# board.net
KiCad netlist of a schematic drawn in EAGLE
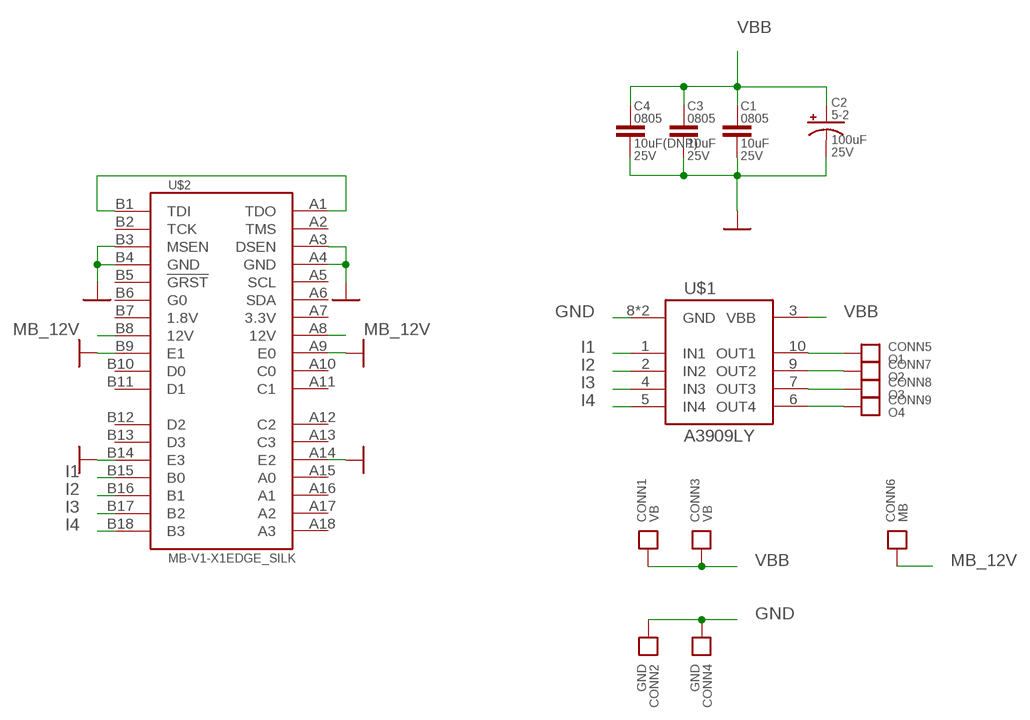
[diagram p0: schematic, sheet 1]

(export (version "E")
  (design (tool "Eeschema 10.0.6"))
  (components
    (comp (ref "C1")
      (value "10uF")
      (footprint "eagle-import:0805-CAP")
      (fields (field (name "VOLTAGE") "6.3V") (field (name "VOLTAGE_1") "25V"))
      (libsource (lib "eagle-import") (part "CAP0805"))
    )
    (comp (ref "C2")
      (value "100uF")
      (footprint "eagle-import:CAP-5-2")
      (fields (field (name "VOLTAGE") "6.3V") (field (name "VOLTAGE_1") "25V"))
      (libsource (lib "eagle-import") (part "CAP_POLPTH-5-2"))
    )
    (comp (ref "C3")
      (value "10uF")
      (footprint "eagle-import:0805-CAP")
      (fields (field (name "VOLTAGE") "6.3V") (field (name "VOLTAGE_1") "25V"))
      (libsource (lib "eagle-import") (part "CAP0805"))
    )
    (comp (ref "C4")
      (value "10uF(DNP)")
      (footprint "eagle-import:0805-CAP")
      (fields (field (name "VOLTAGE") "6.3V") (field (name "VOLTAGE_1") "25V"))
      (libsource (lib "eagle-import") (part "CAP0805"))
    )
    (comp (ref "CONN1")
      (value "VB")
      (footprint "eagle-import:SCREW_5MM")
      (libsource (lib "eagle-import") (part "CONNECTORSCREW_5MM"))
    )
    (comp (ref "CONN2")
      (value "GND")
      (footprint "eagle-import:SCREW_5MM")
      (libsource (lib "eagle-import") (part "CONNECTORSCREW_5MM"))
    )
    (comp (ref "CONN3")
      (value "VB")
      (footprint "eagle-import:SCREW_2.5MM")
      (libsource (lib "eagle-import") (part "CONNECTORSCREW_2.5MM"))
    )
    (comp (ref "CONN4")
      (value "GND")
      (footprint "eagle-import:SCREW_2.5MM")
      (libsource (lib "eagle-import") (part "CONNECTORSCREW_2.5MM"))
    )
    (comp (ref "CONN5")
      (value "O1")
      (footprint "eagle-import:SCREW_2.5MM")
      (libsource (lib "eagle-import") (part "CONNECTORSCREW_2.5MM"))
    )
    (comp (ref "CONN6")
      (value "MB")
      (footprint "eagle-import:SCREW_2.5MM")
      (libsource (lib "eagle-import") (part "CONNECTORSCREW_2.5MM"))
    )
    (comp (ref "CONN7")
      (value "O2")
      (footprint "eagle-import:SCREW_2.5MM")
      (libsource (lib "eagle-import") (part "CONNECTORSCREW_2.5MM"))
    )
    (comp (ref "CONN8")
      (value "O3")
      (footprint "eagle-import:SCREW_2.5MM")
      (libsource (lib "eagle-import") (part "CONNECTORSCREW_2.5MM"))
    )
    (comp (ref "CONN9")
      (value "O4")
      (footprint "eagle-import:SCREW_2.5MM")
      (libsource (lib "eagle-import") (part "CONNECTORSCREW_2.5MM"))
    )
    (comp (ref "U$1")
      (value "A3909LY")
      (footprint "eagle-import:MSOP10")
      (libsource (lib "eagle-import") (part "A3909LY"))
    )
    (comp (ref "U$2")
      (value "MB-V1-X1EDGE_SILK")
      (footprint "eagle-import:MB-V1-X1-EDGE")
      (libsource (lib "eagle-import") (part "MB-V1-X1EDGE_SILK"))
    )
  )
  (nets
    (net (code "1") (name "/I1") (class "Default")
      (node (ref "U$1") (pin "1") (pinfunction "IN1_1") (pintype "bidirectional"))
      (node (ref "U$2") (pin "B15") (pinfunction "B0_B15") (pintype "bidirectional"))
    )
    (net (code "2") (name "/I2") (class "Default")
      (node (ref "U$1") (pin "2") (pinfunction "IN2_2") (pintype "bidirectional"))
      (node (ref "U$2") (pin "B16") (pinfunction "B1_B16") (pintype "bidirectional"))
    )
    (net (code "3") (name "/I3") (class "Default")
      (node (ref "U$1") (pin "4") (pinfunction "IN3_4") (pintype "bidirectional"))
      (node (ref "U$2") (pin "B17") (pinfunction "B2_B17") (pintype "bidirectional"))
    )
    (net (code "4") (name "/I4") (class "Default")
      (node (ref "U$1") (pin "5") (pinfunction "IN4_5") (pintype "bidirectional"))
      (node (ref "U$2") (pin "B18") (pinfunction "B3_B18") (pintype "bidirectional"))
    )
    (net (code "5") (name "/MB_12V") (class "Default")
      (node (ref "CONN6") (pin "P") (pinfunction "P_P") (pintype "bidirectional"))
      (node (ref "U$2") (pin "A8") (pinfunction "12V_A8") (pintype "bidirectional"))
      (node (ref "U$2") (pin "B8") (pinfunction "12V_B8") (pintype "bidirectional"))
    )
    (net (code "6") (name "/VBB") (class "Default")
      (node (ref "C1") (pin "1") (pinfunction "1_1") (pintype "passive"))
      (node (ref "C2") (pin "1") (pinfunction "+_1") (pintype "passive"))
      (node (ref "C3") (pin "1") (pinfunction "1_1") (pintype "passive"))
      (node (ref "C4") (pin "1") (pinfunction "1_1") (pintype "passive"))
      (node (ref "CONN1") (pin "P$1") (pinfunction "P_P$1") (pintype "bidirectional"))
      (node (ref "CONN3") (pin "P") (pinfunction "P_P") (pintype "bidirectional"))
      (node (ref "U$1") (pin "3") (pinfunction "VBB_3") (pintype "input"))
    )
    (net (code "7") (name "GND") (class "Default")
      (node (ref "C1") (pin "2") (pinfunction "2_2") (pintype "passive"))
      (node (ref "C2") (pin "2") (pinfunction "-_2") (pintype "passive"))
      (node (ref "C3") (pin "2") (pinfunction "2_2") (pintype "passive"))
      (node (ref "C4") (pin "2") (pinfunction "2_2") (pintype "passive"))
      (node (ref "CONN2") (pin "P$1") (pinfunction "P_P$1") (pintype "bidirectional"))
      (node (ref "CONN4") (pin "P") (pinfunction "P_P") (pintype "bidirectional"))
      (node (ref "U$1") (pin "8") (pinfunction "GND_8") (pintype "input"))
      (node (ref "U$1") (pin "PAD") (pinfunction "GND_PAD") (pintype "input"))
      (node (ref "U$2") (pin "A14") (pinfunction "E2_A14") (pintype "bidirectional"))
      (node (ref "U$2") (pin "A3") (pinfunction "DSEN_A3") (pintype "bidirectional"))
      (node (ref "U$2") (pin "A4") (pinfunction "GND_A4") (pintype "input"))
      (node (ref "U$2") (pin "A9") (pinfunction "E0_A9") (pintype "bidirectional"))
      (node (ref "U$2") (pin "B14") (pinfunction "E3_B14") (pintype "bidirectional"))
      (node (ref "U$2") (pin "B3") (pinfunction "MSEN_B3") (pintype "bidirectional"))
      (node (ref "U$2") (pin "B4") (pinfunction "GND_B4") (pintype "input"))
      (node (ref "U$2") (pin "B9") (pinfunction "E1_B9") (pintype "bidirectional"))
    )
    (net (code "8") (name "Net-(U$1-OUT1)") (class "Default")
      (node (ref "CONN5") (pin "P") (pinfunction "P_P") (pintype "bidirectional"))
      (node (ref "U$1") (pin "10") (pinfunction "OUT1_10") (pintype "output"))
    )
    (net (code "9") (name "Net-(U$1-OUT2)") (class "Default")
      (node (ref "CONN7") (pin "P") (pinfunction "P_P") (pintype "bidirectional"))
      (node (ref "U$1") (pin "9") (pinfunction "OUT2_9") (pintype "output"))
    )
    (net (code "10") (name "Net-(U$1-OUT3)") (class "Default")
      (node (ref "CONN8") (pin "P") (pinfunction "P_P") (pintype "bidirectional"))
      (node (ref "U$1") (pin "7") (pinfunction "OUT3_7") (pintype "output"))
    )
    (net (code "11") (name "Net-(U$1-OUT4)") (class "Default")
      (node (ref "CONN9") (pin "P") (pinfunction "P_P") (pintype "bidirectional"))
      (node (ref "U$1") (pin "6") (pinfunction "OUT4_6") (pintype "output"))
    )
    (net (code "12") (name "Net-(U$2-TDI)") (class "Default")
      (node (ref "U$2") (pin "A1") (pinfunction "TDO_A1") (pintype "input"))
      (node (ref "U$2") (pin "B1") (pinfunction "TDI_B1") (pintype "output"))
    )
    (net (code "13") (name "unconnected-(U$2-1.8V-PadB7)") (class "Default")
      (node (ref "U$2") (pin "B7") (pinfunction "1.8V_B7") (pintype "bidirectional"))
    )
    (net (code "14") (name "unconnected-(U$2-3.3V-PadA7)") (class "Default")
      (node (ref "U$2") (pin "A7") (pinfunction "3.3V_A7") (pintype "bidirectional"))
    )
    (net (code "15") (name "unconnected-(U$2-A0-PadA15)") (class "Default")
      (node (ref "U$2") (pin "A15") (pinfunction "A0_A15") (pintype "bidirectional"))
    )
    (net (code "16") (name "unconnected-(U$2-A1-PadA16)") (class "Default")
      (node (ref "U$2") (pin "A16") (pinfunction "A1_A16") (pintype "bidirectional"))
    )
    (net (code "17") (name "unconnected-(U$2-A2-PadA17)") (class "Default")
      (node (ref "U$2") (pin "A17") (pinfunction "A2_A17") (pintype "bidirectional"))
    )
    (net (code "18") (name "unconnected-(U$2-A3-PadA18)") (class "Default")
      (node (ref "U$2") (pin "A18") (pinfunction "A3_A18") (pintype "bidirectional"))
    )
    (net (code "19") (name "unconnected-(U$2-C0-PadA10)") (class "Default")
      (node (ref "U$2") (pin "A10") (pinfunction "C0_A10") (pintype "bidirectional"))
    )
    (net (code "20") (name "unconnected-(U$2-C1-PadA11)") (class "Default")
      (node (ref "U$2") (pin "A11") (pinfunction "C1_A11") (pintype "bidirectional"))
    )
    (net (code "21") (name "unconnected-(U$2-C2-PadA12)") (class "Default")
      (node (ref "U$2") (pin "A12") (pinfunction "C2_A12") (pintype "bidirectional"))
    )
    (net (code "22") (name "unconnected-(U$2-C3-PadA13)") (class "Default")
      (node (ref "U$2") (pin "A13") (pinfunction "C3_A13") (pintype "bidirectional"))
    )
    (net (code "23") (name "unconnected-(U$2-D0-PadB10)") (class "Default")
      (node (ref "U$2") (pin "B10") (pinfunction "D0_B10") (pintype "bidirectional"))
    )
    (net (code "24") (name "unconnected-(U$2-D1-PadB11)") (class "Default")
      (node (ref "U$2") (pin "B11") (pinfunction "D1_B11") (pintype "bidirectional"))
    )
    (net (code "25") (name "unconnected-(U$2-D2-PadB12)") (class "Default")
      (node (ref "U$2") (pin "B12") (pinfunction "D2_B12") (pintype "bidirectional"))
    )
    (net (code "26") (name "unconnected-(U$2-D3-PadB13)") (class "Default")
      (node (ref "U$2") (pin "B13") (pinfunction "D3_B13") (pintype "bidirectional"))
    )
    (net (code "27") (name "unconnected-(U$2-G0-PadB6)") (class "Default")
      (node (ref "U$2") (pin "B6") (pinfunction "G0_B6") (pintype "bidirectional"))
    )
    (net (code "28") (name "unconnected-(U$2-SCL-PadA5)") (class "Default")
      (node (ref "U$2") (pin "A5") (pinfunction "SCL_A5") (pintype "bidirectional"))
    )
    (net (code "29") (name "unconnected-(U$2-SDA-PadA6)") (class "Default")
      (node (ref "U$2") (pin "A6") (pinfunction "SDA_A6") (pintype "bidirectional"))
    )
    (net (code "30") (name "unconnected-(U$2-TCK-PadB2)") (class "Default")
      (node (ref "U$2") (pin "B2") (pinfunction "TCK_B2") (pintype "bidirectional"))
    )
    (net (code "31") (name "unconnected-(U$2-TMS-PadA2)") (class "Default")
      (node (ref "U$2") (pin "A2") (pinfunction "TMS_A2") (pintype "bidirectional"))
    )
    (net (code "32") (name "unconnected-(U$2-~{GRST}-PadB5)") (class "Default")
      (node (ref "U$2") (pin "B5") (pinfunction "~{GRST}_B5") (pintype "bidirectional"))
    )
  )
)
